# simp_sensor_v1.net
KiCad netlist of a schematic drawn in Altium Designer
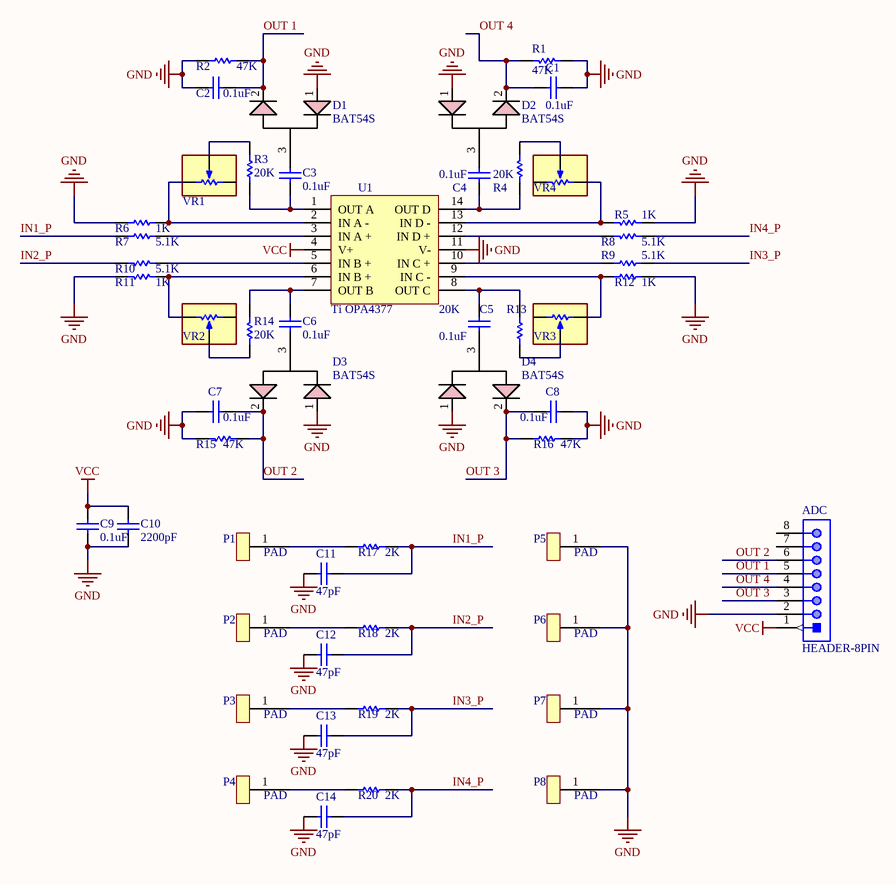
[diagram p0: simp_sensor_v1.SchDoc]

(export (version "E")
  (design (tool "Eeschema 10.0.6"))
  (components
    (comp (ref "ADC")
      (value "HEADER-8PIN")
      (footprint "HEADER_8P_1.25_RT")
      (libsource (lib "My Footprint") (part "HEADER-8PIN"))
    )
    (comp (ref "C1")
      (value "0.1uF")
      (footprint "0603_C")
      (description "Capacitor")
      (fields (field (name "PUBLISHER") "Altium Limited"))
      (libsource (lib "My Footprint") (part "CAP"))
    )
    (comp (ref "C2")
      (value "0.1uF")
      (footprint "0603_C")
      (description "Capacitor")
      (fields (field (name "PUBLISHER") "Altium Limited"))
      (libsource (lib "My Footprint") (part "CAP"))
    )
    (comp (ref "C3")
      (value "0.1uF")
      (footprint "0603_C")
      (description "Capacitor")
      (fields (field (name "PUBLISHER") "Altium Limited"))
      (libsource (lib "My Footprint") (part "CAP"))
    )
    (comp (ref "C4")
      (value "0.1uF")
      (footprint "0603_C")
      (description "Capacitor")
      (fields (field (name "PUBLISHER") "Altium Limited"))
      (libsource (lib "My Footprint") (part "CAP"))
    )
    (comp (ref "C5")
      (value "0.1uF")
      (footprint "0603_C")
      (description "Capacitor")
      (fields (field (name "PUBLISHER") "Altium Limited"))
      (libsource (lib "My Footprint") (part "CAP"))
    )
    (comp (ref "C6")
      (value "0.1uF")
      (footprint "0603_C")
      (description "Capacitor")
      (fields (field (name "PUBLISHER") "Altium Limited"))
      (libsource (lib "My Footprint") (part "CAP"))
    )
    (comp (ref "C7")
      (value "0.1uF")
      (footprint "0603_C")
      (description "Capacitor")
      (fields (field (name "PUBLISHER") "Altium Limited"))
      (libsource (lib "My Footprint") (part "CAP"))
    )
    (comp (ref "C8")
      (value "0.1uF")
      (footprint "0603_C")
      (description "Capacitor")
      (fields (field (name "PUBLISHER") "Altium Limited"))
      (libsource (lib "My Footprint") (part "CAP"))
    )
    (comp (ref "C9")
      (value "0.1uF")
      (footprint "0603_C")
      (description "Capacitor")
      (fields (field (name "PUBLISHER") "Altium Limited"))
      (libsource (lib "My Footprint") (part "CAP"))
    )
    (comp (ref "C10")
      (value "2200pF")
      (footprint "0603_C")
      (description "Capacitor")
      (fields (field (name "PUBLISHER") "Altium Limited"))
      (libsource (lib "My Footprint") (part "CAP"))
    )
    (comp (ref "C11")
      (value "47pF")
      (footprint "0603_C")
      (description "Capacitor")
      (fields (field (name "PUBLISHER") "Altium Limited"))
      (libsource (lib "My Footprint") (part "CAP"))
    )
    (comp (ref "C12")
      (value "47pF")
      (footprint "0603_C")
      (description "Capacitor")
      (fields (field (name "PUBLISHER") "Altium Limited"))
      (libsource (lib "My Footprint") (part "CAP"))
    )
    (comp (ref "C13")
      (value "47pF")
      (footprint "0603_C")
      (description "Capacitor")
      (fields (field (name "PUBLISHER") "Altium Limited"))
      (libsource (lib "My Footprint") (part "CAP"))
    )
    (comp (ref "C14")
      (value "47pF")
      (footprint "0603_C")
      (description "Capacitor")
      (fields (field (name "PUBLISHER") "Altium Limited"))
      (libsource (lib "My Footprint") (part "CAP"))
    )
    (comp (ref "D1")
      (value "BAT54S")
      (footprint "SamacSys:SOT95P240X120-3N")
      (description "Schottky Diode")
      (fields (field (name "MOUSER PART NUMBER") "512-BAT54S") (field (name "RS PART NUMBER") "6708797P"))
      (libsource (lib "SamacSys") (part "BAT54S"))
    )
    (comp (ref "D2")
      (value "BAT54S")
      (footprint "SamacSys:SOT95P240X120-3N")
      (description "Schottky Diode")
      (fields (field (name "MOUSER PART NUMBER") "512-BAT54S") (field (name "RS PART NUMBER") "6708797P"))
      (libsource (lib "SamacSys") (part "BAT54S"))
    )
    (comp (ref "D3")
      (value "BAT54S")
      (footprint "SamacSys:SOT95P240X120-3N")
      (description "Schottky Diode")
      (fields (field (name "MOUSER PART NUMBER") "512-BAT54S") (field (name "RS PART NUMBER") "6708797P"))
      (libsource (lib "SamacSys") (part "BAT54S"))
    )
    (comp (ref "D4")
      (value "BAT54S")
      (footprint "SamacSys:SOT95P240X120-3N")
      (description "Schottky Diode")
      (fields (field (name "MOUSER PART NUMBER") "512-BAT54S") (field (name "RS PART NUMBER") "6708797P"))
      (libsource (lib "SamacSys") (part "BAT54S"))
    )
    (comp (ref "P1") (value "PAD") (footprint "PAD") (libsource (lib "My Footprint") (part "PAD")))
    (comp (ref "P2") (value "PAD") (footprint "PAD") (libsource (lib "My Footprint") (part "PAD")))
    (comp (ref "P3") (value "PAD") (footprint "PAD") (libsource (lib "My Footprint") (part "PAD")))
    (comp (ref "P4") (value "PAD") (footprint "PAD") (libsource (lib "My Footprint") (part "PAD")))
    (comp (ref "P5") (value "PAD") (footprint "PAD") (libsource (lib "My Footprint") (part "PAD")))
    (comp (ref "P6") (value "PAD") (footprint "PAD") (libsource (lib "My Footprint") (part "PAD")))
    (comp (ref "P7") (value "PAD") (footprint "PAD") (libsource (lib "My Footprint") (part "PAD")))
    (comp (ref "P8") (value "PAD") (footprint "PAD") (libsource (lib "My Footprint") (part "PAD")))
    (comp (ref "R1")
      (value "47K")
      (footprint "0603_R")
      (description "Resistor")
      (fields (field (name "PUBLISHER") "Altium Limited"))
      (libsource (lib "My Footprint") (part "RES0"))
    )
    (comp (ref "R2")
      (value "47K")
      (footprint "0603_R")
      (description "Resistor")
      (fields (field (name "PUBLISHER") "Altium Limited"))
      (libsource (lib "My Footprint") (part "RES0"))
    )
    (comp (ref "R3")
      (value "20K")
      (footprint "0603_R")
      (description "Resistor")
      (fields (field (name "PUBLISHER") "Altium Limited"))
      (libsource (lib "My Footprint") (part "RES0"))
    )
    (comp (ref "R4")
      (value "20K")
      (footprint "0603_R")
      (description "Resistor")
      (fields (field (name "PUBLISHER") "Altium Limited"))
      (libsource (lib "My Footprint") (part "RES0"))
    )
    (comp (ref "R5")
      (value "1K")
      (footprint "0603_R")
      (description "Resistor")
      (fields (field (name "PUBLISHER") "Altium Limited"))
      (libsource (lib "My Footprint") (part "RES0"))
    )
    (comp (ref "R6")
      (value "1K")
      (footprint "0603_R")
      (description "Resistor")
      (fields (field (name "PUBLISHER") "Altium Limited"))
      (libsource (lib "My Footprint") (part "RES0"))
    )
    (comp (ref "R7")
      (value "5.1K")
      (footprint "0603_R")
      (description "Resistor")
      (fields (field (name "PUBLISHER") "Altium Limited"))
      (libsource (lib "My Footprint") (part "RES0"))
    )
    (comp (ref "R8")
      (value "5.1K")
      (footprint "0603_R")
      (description "Resistor")
      (fields (field (name "PUBLISHER") "Altium Limited"))
      (libsource (lib "My Footprint") (part "RES0"))
    )
    (comp (ref "R9")
      (value "5.1K")
      (footprint "0603_R")
      (description "Resistor")
      (fields (field (name "PUBLISHER") "Altium Limited"))
      (libsource (lib "My Footprint") (part "RES0"))
    )
    (comp (ref "R10")
      (value "5.1K")
      (footprint "0603_R")
      (description "Resistor")
      (fields (field (name "PUBLISHER") "Altium Limited"))
      (libsource (lib "My Footprint") (part "RES0"))
    )
    (comp (ref "R11")
      (value "1K")
      (footprint "0603_R")
      (description "Resistor")
      (fields (field (name "PUBLISHER") "Altium Limited"))
      (libsource (lib "My Footprint") (part "RES0"))
    )
    (comp (ref "R12")
      (value "1K")
      (footprint "0603_R")
      (description "Resistor")
      (fields (field (name "PUBLISHER") "Altium Limited"))
      (libsource (lib "My Footprint") (part "RES0"))
    )
    (comp (ref "R13")
      (value "20K")
      (footprint "0603_R")
      (description "Resistor")
      (fields (field (name "PUBLISHER") "Altium Limited"))
      (libsource (lib "My Footprint") (part "RES0"))
    )
    (comp (ref "R14")
      (value "20K")
      (footprint "0603_R")
      (description "Resistor")
      (fields (field (name "PUBLISHER") "Altium Limited"))
      (libsource (lib "My Footprint") (part "RES0"))
    )
    (comp (ref "R15")
      (value "47K")
      (footprint "0603_R")
      (description "Resistor")
      (fields (field (name "PUBLISHER") "Altium Limited"))
      (libsource (lib "My Footprint") (part "RES0"))
    )
    (comp (ref "R16")
      (value "47K")
      (footprint "0603_R")
      (description "Resistor")
      (fields (field (name "PUBLISHER") "Altium Limited"))
      (libsource (lib "My Footprint") (part "RES0"))
    )
    (comp (ref "R17")
      (value "2K")
      (footprint "0603_R")
      (description "Resistor")
      (fields (field (name "PUBLISHER") "Altium Limited"))
      (libsource (lib "My Footprint") (part "RES0"))
    )
    (comp (ref "R18")
      (value "2K")
      (footprint "0603_R")
      (description "Resistor")
      (fields (field (name "PUBLISHER") "Altium Limited"))
      (libsource (lib "My Footprint") (part "RES0"))
    )
    (comp (ref "R19")
      (value "2K")
      (footprint "0603_R")
      (description "Resistor")
      (fields (field (name "PUBLISHER") "Altium Limited"))
      (libsource (lib "My Footprint") (part "RES0"))
    )
    (comp (ref "R20")
      (value "2K")
      (footprint "0603_R")
      (description "Resistor")
      (fields (field (name "PUBLISHER") "Altium Limited"))
      (libsource (lib "My Footprint") (part "RES0"))
    )
    (comp (ref "U1") (value "Ti OPA4377") (footprint "TSSOP14") (libsource (lib "SamacSys") (part "opa4377")))
    (comp (ref "VR1")
      (value "3224W-1-101G")
      (footprint "SamacSys:3224W1101G")
      (description "Variable Resistor")
      (fields (field (name "MOUSER PART NUMBER") "652-3224W-1-101G"))
      (libsource (lib "") (part "3224W-1-101G_1"))
    )
    (comp (ref "VR2")
      (value "3224W-1-101G")
      (footprint "SamacSys:3224W1101G")
      (description "Variable Resistor")
      (fields (field (name "MOUSER PART NUMBER") "652-3224W-1-101G"))
      (libsource (lib "") (part "3224W-1-101G_2"))
    )
    (comp (ref "VR3")
      (value "3224W-1-101G")
      (footprint "SamacSys:3224W1101G")
      (description "Variable Resistor")
      (fields (field (name "MOUSER PART NUMBER") "652-3224W-1-101G"))
      (libsource (lib "SamacSys") (part "3224W-1-101G"))
    )
    (comp (ref "VR4")
      (value "3224W-1-101G")
      (footprint "SamacSys:3224W1101G")
      (description "Variable Resistor")
      (fields (field (name "MOUSER PART NUMBER") "652-3224W-1-101G"))
      (libsource (lib "") (part "3224W-1-101G_3"))
    )
  )
  (nets
    (net (code "1") (name "/IN1_P") (class "Default")
      (node (ref "C11") (pin "2") (pinfunction "2_2") (pintype "passive"))
      (node (ref "R17") (pin "1") (pinfunction "1_1") (pintype "passive"))
      (node (ref "R7") (pin "1") (pinfunction "1_1") (pintype "passive"))
    )
    (net (code "2") (name "/IN2_P") (class "Default")
      (node (ref "C12") (pin "2") (pinfunction "2_2") (pintype "passive"))
      (node (ref "R10") (pin "1") (pinfunction "1_1") (pintype "passive"))
      (node (ref "R18") (pin "1") (pinfunction "1_1") (pintype "passive"))
    )
    (net (code "3") (name "/IN3_P") (class "Default")
      (node (ref "C13") (pin "2") (pinfunction "2_2") (pintype "passive"))
      (node (ref "R19") (pin "1") (pinfunction "1_1") (pintype "passive"))
      (node (ref "R9") (pin "1") (pinfunction "1_1") (pintype "passive"))
    )
    (net (code "4") (name "/IN4_P") (class "Default")
      (node (ref "C14") (pin "2") (pinfunction "2_2") (pintype "passive"))
      (node (ref "R20") (pin "1") (pinfunction "1_1") (pintype "passive"))
      (node (ref "R8") (pin "1") (pinfunction "1_1") (pintype "passive"))
    )
    (net (code "5") (name "/OUT 1") (class "Default")
      (node (ref "ADC") (pin "5") (pinfunction "5_5") (pintype "passive"))
      (node (ref "C2") (pin "1") (pinfunction "1_1") (pintype "passive"))
      (node (ref "D1") (pin "2") (pinfunction "K_2") (pintype "passive"))
      (node (ref "R2") (pin "2") (pinfunction "2_2") (pintype "passive"))
    )
    (net (code "6") (name "/OUT 2") (class "Default")
      (node (ref "ADC") (pin "6") (pinfunction "6_6") (pintype "passive"))
      (node (ref "C7") (pin "1") (pinfunction "1_1") (pintype "passive"))
      (node (ref "D3") (pin "2") (pinfunction "K_2") (pintype "passive"))
      (node (ref "R15") (pin "2") (pinfunction "2_2") (pintype "passive"))
    )
    (net (code "7") (name "/OUT 3") (class "Default")
      (node (ref "ADC") (pin "3") (pinfunction "3_3") (pintype "passive"))
      (node (ref "C8") (pin "1") (pinfunction "1_1") (pintype "passive"))
      (node (ref "D4") (pin "2") (pinfunction "K_2") (pintype "passive"))
      (node (ref "R16") (pin "2") (pinfunction "2_2") (pintype "passive"))
    )
    (net (code "8") (name "/OUT 4") (class "Default")
      (node (ref "ADC") (pin "4") (pinfunction "4_4") (pintype "passive"))
      (node (ref "C1") (pin "1") (pinfunction "1_1") (pintype "passive"))
      (node (ref "D2") (pin "2") (pinfunction "K_2") (pintype "passive"))
      (node (ref "R1") (pin "2") (pinfunction "2_2") (pintype "passive"))
    )
    (net (code "9") (name "GND") (class "Default")
      (node (ref "ADC") (pin "2") (pinfunction "2_2") (pintype "passive"))
      (node (ref "C1") (pin "2") (pinfunction "2_2") (pintype "passive"))
      (node (ref "C10") (pin "1") (pinfunction "1_1") (pintype "passive"))
      (node (ref "C11") (pin "1") (pinfunction "1_1") (pintype "passive"))
      (node (ref "C12") (pin "1") (pinfunction "1_1") (pintype "passive"))
      (node (ref "C13") (pin "1") (pinfunction "1_1") (pintype "passive"))
      (node (ref "C14") (pin "1") (pinfunction "1_1") (pintype "passive"))
      (node (ref "C2") (pin "2") (pinfunction "2_2") (pintype "passive"))
      (node (ref "C7") (pin "2") (pinfunction "2_2") (pintype "passive"))
      (node (ref "C8") (pin "2") (pinfunction "2_2") (pintype "passive"))
      (node (ref "C9") (pin "1") (pinfunction "1_1") (pintype "passive"))
      (node (ref "D1") (pin "1") (pinfunction "A_1") (pintype "passive"))
      (node (ref "D2") (pin "1") (pinfunction "A_1") (pintype "passive"))
      (node (ref "D3") (pin "1") (pinfunction "A_1") (pintype "passive"))
      (node (ref "D4") (pin "1") (pinfunction "A_1") (pintype "passive"))
      (node (ref "P5") (pin "1") (pintype "passive"))
      (node (ref "P6") (pin "1") (pintype "passive"))
      (node (ref "P7") (pin "1") (pintype "passive"))
      (node (ref "P8") (pin "1") (pintype "passive"))
      (node (ref "R1") (pin "1") (pinfunction "1_1") (pintype "passive"))
      (node (ref "R11") (pin "1") (pinfunction "1_1") (pintype "passive"))
      (node (ref "R12") (pin "1") (pinfunction "1_1") (pintype "passive"))
      (node (ref "R15") (pin "1") (pinfunction "1_1") (pintype "passive"))
      (node (ref "R16") (pin "1") (pinfunction "1_1") (pintype "passive"))
      (node (ref "R2") (pin "1") (pinfunction "1_1") (pintype "passive"))
      (node (ref "R5") (pin "1") (pinfunction "1_1") (pintype "passive"))
      (node (ref "R6") (pin "1") (pinfunction "1_1") (pintype "passive"))
      (node (ref "U1") (pin "11") (pinfunction "V-_11") (pintype "passive"))
    )
    (net (code "10") (name "Net-(D1-A{slash}K)") (class "Default")
      (node (ref "C3") (pin "1") (pinfunction "1_1") (pintype "passive"))
      (node (ref "D1") (pin "3") (pinfunction "A/K_3") (pintype "passive"))
    )
    (net (code "11") (name "Net-(D2-A{slash}K)") (class "Default")
      (node (ref "C4") (pin "1") (pinfunction "1_1") (pintype "passive"))
      (node (ref "D2") (pin "3") (pinfunction "A/K_3") (pintype "passive"))
    )
    (net (code "12") (name "Net-(D3-A{slash}K)") (class "Default")
      (node (ref "C6") (pin "1") (pinfunction "1_1") (pintype "passive"))
      (node (ref "D3") (pin "3") (pinfunction "A/K_3") (pintype "passive"))
    )
    (net (code "13") (name "Net-(D4-A{slash}K)") (class "Default")
      (node (ref "C5") (pin "1") (pinfunction "1_1") (pintype "passive"))
      (node (ref "D4") (pin "3") (pinfunction "A/K_3") (pintype "passive"))
    )
    (net (code "14") (name "Net-(P1-Pad1)") (class "Default")
      (node (ref "P1") (pin "1") (pintype "passive"))
      (node (ref "R17") (pin "2") (pinfunction "2_2") (pintype "passive"))
    )
    (net (code "15") (name "Net-(P2-Pad1)") (class "Default")
      (node (ref "P2") (pin "1") (pintype "passive"))
      (node (ref "R18") (pin "2") (pinfunction "2_2") (pintype "passive"))
    )
    (net (code "16") (name "Net-(P3-Pad1)") (class "Default")
      (node (ref "P3") (pin "1") (pintype "passive"))
      (node (ref "R19") (pin "2") (pinfunction "2_2") (pintype "passive"))
    )
    (net (code "17") (name "Net-(P4-Pad1)") (class "Default")
      (node (ref "P4") (pin "1") (pintype "passive"))
      (node (ref "R20") (pin "2") (pinfunction "2_2") (pintype "passive"))
    )
    (net (code "18") (name "Net-(R10-Pad2)") (class "Default")
      (node (ref "R10") (pin "2") (pinfunction "2_2") (pintype "passive"))
      (node (ref "U1") (pin "5") (pinfunction "IN_B_+_5") (pintype "passive"))
    )
    (net (code "19") (name "Net-(U1-IN_A_+)") (class "Default")
      (node (ref "R7") (pin "2") (pinfunction "2_2") (pintype "passive"))
      (node (ref "U1") (pin "3") (pinfunction "IN_A_+_3") (pintype "passive"))
    )
    (net (code "20") (name "Net-(U1-IN_A_-)") (class "Default")
      (node (ref "R6") (pin "2") (pinfunction "2_2") (pintype "passive"))
      (node (ref "U1") (pin "2") (pinfunction "IN_A_-_2") (pintype "passive"))
      (node (ref "VR1") (pin "3") (pinfunction "BOT_3") (pintype "passive"))
    )
    (net (code "21") (name "Net-(U1-IN_C_+)") (class "Default")
      (node (ref "R9") (pin "2") (pinfunction "2_2") (pintype "passive"))
      (node (ref "U1") (pin "10") (pinfunction "IN_C_+_10") (pintype "passive"))
    )
    (net (code "22") (name "Net-(U1-IN_C_-)") (class "Default")
      (node (ref "R12") (pin "2") (pinfunction "2_2") (pintype "passive"))
      (node (ref "U1") (pin "9") (pinfunction "IN_C_-_9") (pintype "passive"))
      (node (ref "VR3") (pin "3") (pinfunction "BOT_3") (pintype "passive"))
    )
    (net (code "23") (name "Net-(U1-IN_D_+)") (class "Default")
      (node (ref "R8") (pin "2") (pinfunction "2_2") (pintype "passive"))
      (node (ref "U1") (pin "12") (pinfunction "IN_D_+_12") (pintype "passive"))
    )
    (net (code "24") (name "Net-(U1-IN_D_-)") (class "Default")
      (node (ref "R5") (pin "2") (pinfunction "2_2") (pintype "passive"))
      (node (ref "U1") (pin "13") (pinfunction "IN_D_-_13") (pintype "passive"))
      (node (ref "VR4") (pin "3") (pinfunction "BOT_3") (pintype "passive"))
    )
    (net (code "25") (name "Net-(U1-OUT_A)") (class "Default")
      (node (ref "C3") (pin "2") (pinfunction "2_2") (pintype "passive"))
      (node (ref "R3") (pin "2") (pinfunction "2_2") (pintype "passive"))
      (node (ref "U1") (pin "1") (pinfunction "OUT_A_1") (pintype "passive"))
    )
    (net (code "26") (name "Net-(U1-OUT_B)") (class "Default")
      (node (ref "C6") (pin "2") (pinfunction "2_2") (pintype "passive"))
      (node (ref "R14") (pin "2") (pinfunction "2_2") (pintype "passive"))
      (node (ref "U1") (pin "7") (pinfunction "OUT_B_7") (pintype "passive"))
    )
    (net (code "27") (name "Net-(U1-OUT_C)") (class "Default")
      (node (ref "C5") (pin "2") (pinfunction "2_2") (pintype "passive"))
      (node (ref "R13") (pin "2") (pinfunction "2_2") (pintype "passive"))
      (node (ref "U1") (pin "8") (pinfunction "OUT_C_8") (pintype "passive"))
    )
    (net (code "28") (name "Net-(U1-OUT_D)") (class "Default")
      (node (ref "C4") (pin "2") (pinfunction "2_2") (pintype "passive"))
      (node (ref "R4") (pin "2") (pinfunction "2_2") (pintype "passive"))
      (node (ref "U1") (pin "14") (pinfunction "OUT_D_14") (pintype "passive"))
    )
    (net (code "29") (name "Net-(VR1-TAP)") (class "Default")
      (node (ref "R3") (pin "1") (pinfunction "1_1") (pintype "passive"))
      (node (ref "VR1") (pin "2") (pinfunction "TAP_2") (pintype "passive"))
    )
    (net (code "30") (name "Net-(VR2-BOT)") (class "Default")
      (node (ref "R11") (pin "2") (pinfunction "2_2") (pintype "passive"))
      (node (ref "U1") (pin "6") (pinfunction "IN_B_+_6") (pintype "passive"))
      (node (ref "VR2") (pin "3") (pinfunction "BOT_3") (pintype "passive"))
    )
    (net (code "31") (name "Net-(VR2-TAP)") (class "Default")
      (node (ref "R14") (pin "1") (pinfunction "1_1") (pintype "passive"))
      (node (ref "VR2") (pin "2") (pinfunction "TAP_2") (pintype "passive"))
    )
    (net (code "32") (name "Net-(VR3-TAP)") (class "Default")
      (node (ref "R13") (pin "1") (pinfunction "1_1") (pintype "passive"))
      (node (ref "VR3") (pin "2") (pinfunction "TAP_2") (pintype "passive"))
    )
    (net (code "33") (name "Net-(VR4-TAP)") (class "Default")
      (node (ref "R4") (pin "1") (pinfunction "1_1") (pintype "passive"))
      (node (ref "VR4") (pin "2") (pinfunction "TAP_2") (pintype "passive"))
    )
    (net (code "34") (name "VCC") (class "Default")
      (node (ref "ADC") (pin "1") (pinfunction "1_1") (pintype "output"))
      (node (ref "C10") (pin "2") (pinfunction "2_2") (pintype "passive"))
      (node (ref "C9") (pin "2") (pinfunction "2_2") (pintype "passive"))
      (node (ref "U1") (pin "4") (pinfunction "V+_4") (pintype "passive"))
    )
    (net (code "35") (name "unconnected-(ADC-Pad7)") (class "Default")
      (node (ref "ADC") (pin "7") (pinfunction "7_7") (pintype "passive"))
    )
    (net (code "36") (name "unconnected-(ADC-Pad8)") (class "Default")
      (node (ref "ADC") (pin "8") (pinfunction "8_8") (pintype "passive"))
    )
    (net (code "37") (name "unconnected-(VR1-TOP-Pad1)") (class "Default")
      (node (ref "VR1") (pin "1") (pinfunction "TOP_1") (pintype "passive"))
    )
    (net (code "38") (name "unconnected-(VR2-TOP-Pad1)") (class "Default")
      (node (ref "VR2") (pin "1") (pinfunction "TOP_1") (pintype "passive"))
    )
    (net (code "39") (name "unconnected-(VR3-TOP-Pad1)") (class "Default")
      (node (ref "VR3") (pin "1") (pinfunction "TOP_1") (pintype "passive"))
    )
    (net (code "40") (name "unconnected-(VR4-TOP-Pad1)") (class "Default")
      (node (ref "VR4") (pin "1") (pinfunction "TOP_1") (pintype "passive"))
    )
  )
)
